# Microcontroller.net
KiCad netlist of a schematic drawn in Altium Designer
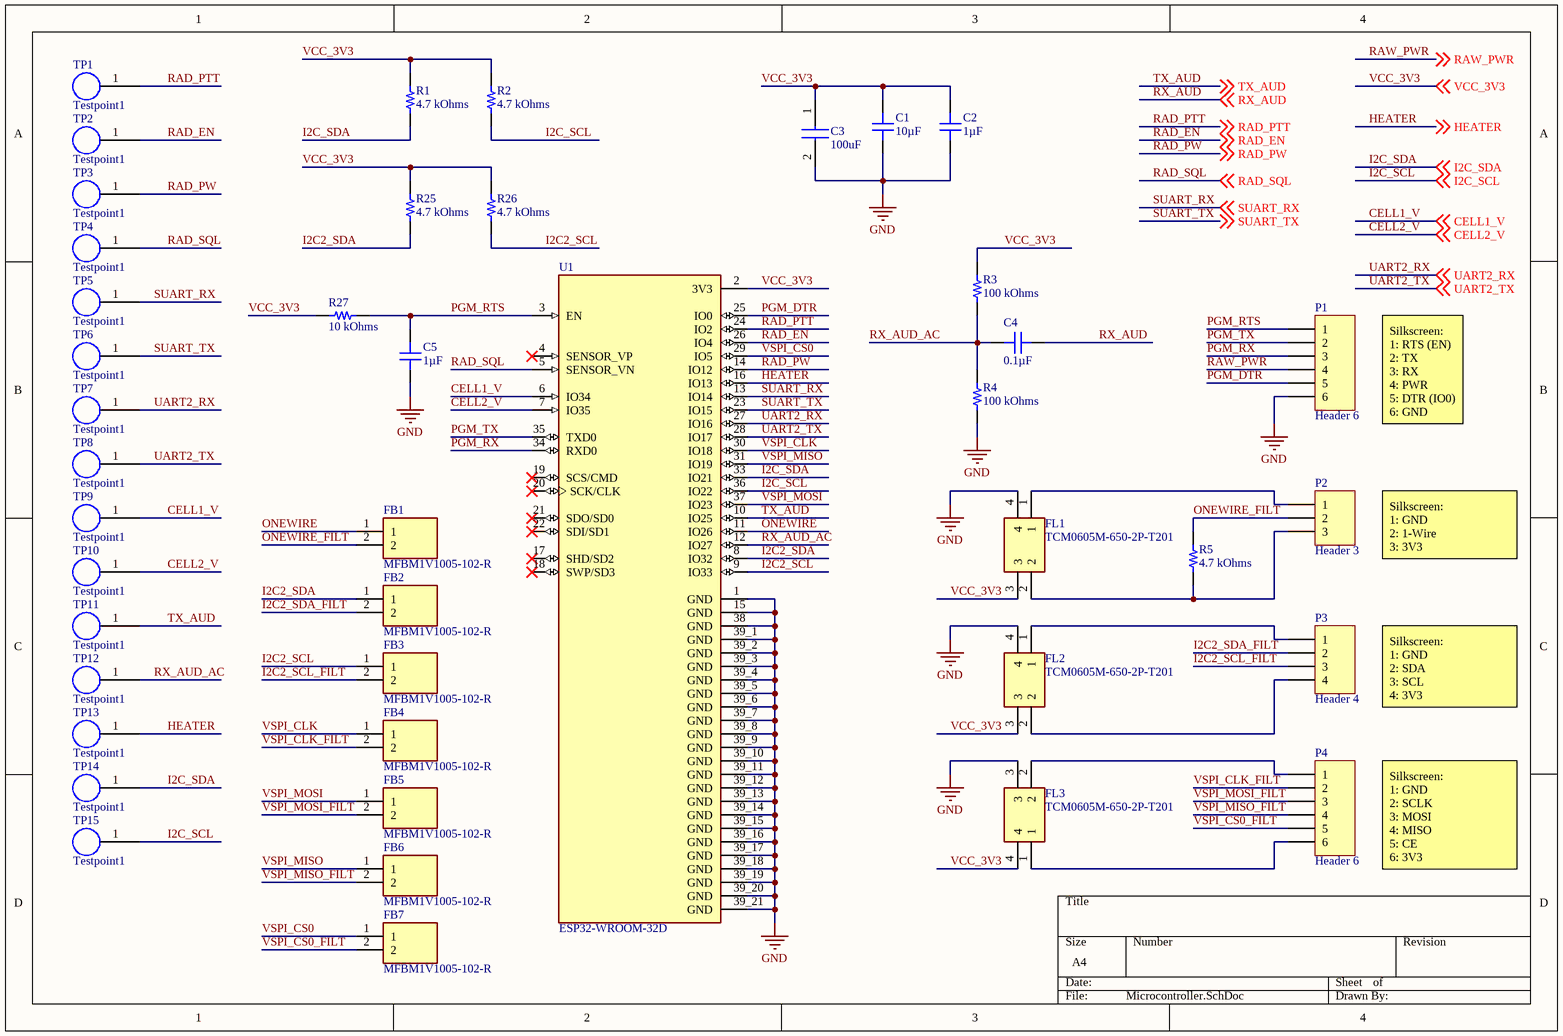
[diagram p0: Microcontroller.SchDoc]

(export (version "E")
  (design (tool "Eeschema 10.0.6"))
  (components
    (comp (ref "C1")
      (value "10µF")
      (footprint "CAP 0402_1005")
      (description "CAP CER 10UF 6.3V X5R 0402")
      (fields (field (name "PART NUMBER") "C0402C106M9PAC7867") (field (name "MANUFACTURER") "KEMET"))
      (libsource (lib "Celestial Altium Library - altium_library") (part "Capacitor"))
    )
    (comp (ref "C2")
      (value "1µF")
      (footprint "CAP 0402_1005")
      (description "CAP CER 1UF 16V X5R 0402")
      (fields (field (name "PART NUMBER") "0402YD105KAT2A") (field (name "MANUFACTURER") "AVX Corporation"))
      (libsource (lib "Celestial Altium Library - altium_library") (part "Capacitor"))
    )
    (comp (ref "C3")
      (value "100uF")
      (footprint "SamacSys:CAPC3225X270N")
      (description "Capacitor")
      (fields
        (field (name "MOUSER2 PART NUMBER") "81-GRM32EC70J107ME5L")
        (field (name "MANUFACTURER_PART_NUMBER") "GRM32EC70J107ME15L")
      )
      (libsource (lib "*") (part "GRM32EC70J107ME15L"))
    )
    (comp (ref "C4")
      (value "0.1µF")
      (footprint "CAP 0402_1005")
      (description "CAP CER 0.1UF 6.3V X5R 0402")
      (fields (field (name "PART NUMBER") "C0402C104K9PACTU") (field (name "MANUFACTURER") "KEMET"))
      (libsource (lib "Celestial Altium Library - altium_library") (part "Capacitor"))
    )
    (comp (ref "C5")
      (value "1µF")
      (footprint "CAP 0402_1005")
      (description "CAP CER 1UF 16V X5R 0402")
      (fields (field (name "PART NUMBER") "0402YD105KAT2A") (field (name "MANUFACTURER") "AVX Corporation"))
      (libsource (lib "Celestial Altium Library - altium_library") (part "Capacitor"))
    )
    (comp (ref "FB1")
      (value "MFBM1V1005-102-R")
      (footprint "SamacSys:BEADC1005X65N")
      (description "Ferrite Bead")
      (fields (field (name "MANUFACTURER_PART_NUMBER") "MFBM1V1005-101-R"))
      (libsource (lib "SamacSys") (part "MFBM1V1005-102-R"))
    )
    (comp (ref "FB2")
      (value "MFBM1V1005-102-R")
      (footprint "SamacSys:BEADC1005X65N")
      (description "Ferrite Bead")
      (fields (field (name "MANUFACTURER_PART_NUMBER") "MFBM1V1005-101-R"))
      (libsource (lib "SamacSys") (part "MFBM1V1005-102-R"))
    )
    (comp (ref "FB3")
      (value "MFBM1V1005-102-R")
      (footprint "SamacSys:BEADC1005X65N")
      (description "Ferrite Bead")
      (fields (field (name "MANUFACTURER_PART_NUMBER") "MFBM1V1005-101-R"))
      (libsource (lib "SamacSys") (part "MFBM1V1005-102-R"))
    )
    (comp (ref "FB4")
      (value "MFBM1V1005-102-R")
      (footprint "SamacSys:BEADC1005X65N")
      (description "Ferrite Bead")
      (fields (field (name "MANUFACTURER_PART_NUMBER") "MFBM1V1005-101-R"))
      (libsource (lib "SamacSys") (part "MFBM1V1005-102-R"))
    )
    (comp (ref "FB5")
      (value "MFBM1V1005-102-R")
      (footprint "SamacSys:BEADC1005X65N")
      (description "Ferrite Bead")
      (fields (field (name "MANUFACTURER_PART_NUMBER") "MFBM1V1005-101-R"))
      (libsource (lib "SamacSys") (part "MFBM1V1005-102-R"))
    )
    (comp (ref "FB6")
      (value "MFBM1V1005-102-R")
      (footprint "SamacSys:BEADC1005X65N")
      (description "Ferrite Bead")
      (fields (field (name "MANUFACTURER_PART_NUMBER") "MFBM1V1005-101-R"))
      (libsource (lib "SamacSys") (part "MFBM1V1005-102-R"))
    )
    (comp (ref "FB7")
      (value "MFBM1V1005-102-R")
      (footprint "SamacSys:BEADC1005X65N")
      (description "Ferrite Bead")
      (fields (field (name "MANUFACTURER_PART_NUMBER") "MFBM1V1005-101-R"))
      (libsource (lib "SamacSys") (part "MFBM1V1005-102-R"))
    )
    (comp (ref "FL1")
      (value "TCM0605M-650-2P-T201")
      (footprint "SamacSys:TCM0605M")
      (description "Filter")
      (libsource (lib "*") (part "TCM0605M-650-2P-T201"))
    )
    (comp (ref "FL2")
      (value "TCM0605M-650-2P-T201")
      (footprint "SamacSys:TCM0605M")
      (description "Filter")
      (libsource (lib "*") (part "TCM0605M-650-2P-T201"))
    )
    (comp (ref "FL3")
      (value "TCM0605M-650-2P-T201")
      (footprint "SamacSys:TCM0605M")
      (description "Filter")
      (libsource (lib "") (part "TCM0605M-650-2P-T201_1"))
    )
    (comp (ref "P1")
      (value "Header 6")
      (footprint "HDR1X6")
      (description "Header, 6-Pin")
      (fields (field (name "PUBLISHER") "Altium Limited"))
      (libsource (lib "Miscellaneous Connectors") (part "Header 6"))
    )
    (comp (ref "P2")
      (value "Header 3")
      (footprint "HDR1X3")
      (description "Header, 3-Pin")
      (fields (field (name "PUBLISHER") "Altium Limited"))
      (libsource (lib "Miscellaneous Connectors") (part "Header 3"))
    )
    (comp (ref "P3")
      (value "Header 4")
      (footprint "HDR1X4")
      (description "Header, 4-Pin")
      (fields (field (name "PUBLISHER") "Altium Limited"))
      (libsource (lib "Miscellaneous Connectors") (part "Header 4"))
    )
    (comp (ref "P4")
      (value "Header 6")
      (footprint "HDR1X6")
      (description "Header, 6-Pin")
      (fields (field (name "PUBLISHER") "Altium Limited"))
      (libsource (lib "Miscellaneous Connectors") (part "Header 6"))
    )
    (comp (ref "R1")
      (value "4.7 kOhms")
      (footprint "RES 0402_1005")
      (description "RES SMD 4.7K OHM 5% 1/16W 0402")
      (fields (field (name "PART NUMBER") "CRCW04024K70JNEDC") (field (name "MANUFACTURER") "Vishay Dale"))
      (libsource (lib "Celestial Altium Library - altium_library") (part "Resistor"))
    )
    (comp (ref "R2")
      (value "4.7 kOhms")
      (footprint "RES 0402_1005")
      (description "RES SMD 4.7K OHM 5% 1/16W 0402")
      (fields (field (name "PART NUMBER") "CRCW04024K70JNEDC") (field (name "MANUFACTURER") "Vishay Dale"))
      (libsource (lib "Celestial Altium Library - altium_library") (part "Resistor"))
    )
    (comp (ref "R3")
      (value "100 kOhms")
      (footprint "RES 0402_1005")
      (description "RES SMD 100K OHM 1% 1/16W 0402")
      (fields (field (name "PART NUMBER") "AC0402FR-07100KL") (field (name "MANUFACTURER") "Yageo"))
      (libsource (lib "Celestial Altium Library - altium_library") (part "Resistor"))
    )
    (comp (ref "R4")
      (value "100 kOhms")
      (footprint "RES 0402_1005")
      (description "RES SMD 100K OHM 1% 1/16W 0402")
      (fields (field (name "PART NUMBER") "AC0402FR-07100KL") (field (name "MANUFACTURER") "Yageo"))
      (libsource (lib "Celestial Altium Library - altium_library") (part "Resistor"))
    )
    (comp (ref "R5")
      (value "4.7 kOhms")
      (footprint "RES 0402_1005")
      (description "RES SMD 4.7K OHM 5% 1/16W 0402")
      (fields (field (name "PART NUMBER") "CRCW04024K70JNEDC") (field (name "MANUFACTURER") "Vishay Dale"))
      (libsource (lib "Celestial Altium Library - altium_library") (part "Resistor"))
    )
    (comp (ref "R25")
      (value "4.7 kOhms")
      (footprint "RES 0402_1005")
      (description "RES SMD 4.7K OHM 5% 1/16W 0402")
      (fields (field (name "PART NUMBER") "CRCW04024K70JNEDC") (field (name "MANUFACTURER") "Vishay Dale"))
      (libsource (lib "Celestial Altium Library - altium_library") (part "Resistor"))
    )
    (comp (ref "R26")
      (value "4.7 kOhms")
      (footprint "RES 0402_1005")
      (description "RES SMD 4.7K OHM 5% 1/16W 0402")
      (fields (field (name "PART NUMBER") "CRCW04024K70JNEDC") (field (name "MANUFACTURER") "Vishay Dale"))
      (libsource (lib "Celestial Altium Library - altium_library") (part "Resistor"))
    )
    (comp (ref "R27")
      (value "10 kOhms")
      (footprint "RES 0402_1005")
      (description "RES SMD 10K OHM 0.1% 1/16W 0402")
      (fields
        (field (name "PART NUMBER") "CPF0402B10KE1")
        (field (name "MANUFACTURER") "TE Connectivity Passive Product")
      )
      (libsource (lib "Celestial Altium Library - altium_library") (part "Resistor"))
    )
    (comp (ref "TP1")
      (value "Testpoint1")
      (footprint "Testpoint1")
      (libsource (lib "SamacSys") (part "Testpoint1"))
    )
    (comp (ref "TP2")
      (value "Testpoint1")
      (footprint "Testpoint1")
      (libsource (lib "SamacSys") (part "Testpoint1"))
    )
    (comp (ref "TP3")
      (value "Testpoint1")
      (footprint "Testpoint1")
      (libsource (lib "SamacSys") (part "Testpoint1"))
    )
    (comp (ref "TP4")
      (value "Testpoint1")
      (footprint "Testpoint1")
      (libsource (lib "SamacSys") (part "Testpoint1"))
    )
    (comp (ref "TP5")
      (value "Testpoint1")
      (footprint "Testpoint1")
      (libsource (lib "SamacSys") (part "Testpoint1"))
    )
    (comp (ref "TP6")
      (value "Testpoint1")
      (footprint "Testpoint1")
      (libsource (lib "SamacSys") (part "Testpoint1"))
    )
    (comp (ref "TP7")
      (value "Testpoint1")
      (footprint "Testpoint1")
      (libsource (lib "SamacSys") (part "Testpoint1"))
    )
    (comp (ref "TP8")
      (value "Testpoint1")
      (footprint "Testpoint1")
      (libsource (lib "SamacSys") (part "Testpoint1"))
    )
    (comp (ref "TP9")
      (value "Testpoint1")
      (footprint "Testpoint1")
      (libsource (lib "SamacSys") (part "Testpoint1"))
    )
    (comp (ref "TP10")
      (value "Testpoint1")
      (footprint "Testpoint1")
      (libsource (lib "SamacSys") (part "Testpoint1"))
    )
    (comp (ref "TP11")
      (value "Testpoint1")
      (footprint "Testpoint1")
      (libsource (lib "SamacSys") (part "Testpoint1"))
    )
    (comp (ref "TP12")
      (value "Testpoint1")
      (footprint "Testpoint1")
      (libsource (lib "SamacSys") (part "Testpoint1"))
    )
    (comp (ref "TP13")
      (value "Testpoint1")
      (footprint "Testpoint1")
      (libsource (lib "SamacSys") (part "Testpoint1"))
    )
    (comp (ref "TP14")
      (value "Testpoint1")
      (footprint "Testpoint1")
      (libsource (lib "SamacSys") (part "Testpoint1"))
    )
    (comp (ref "TP15")
      (value "Testpoint1")
      (footprint "Testpoint1")
      (libsource (lib "SamacSys") (part "Testpoint1"))
    )
    (comp (ref "U1")
      (value "ESP32-WROOM-32D")
      (footprint "MODULE_ESP32-WROOM-32D")
      (fields (field (name "MF") "Espressif Systems"))
      (libsource (lib "ESP32-WROOM-32D") (part "ESP32-WROOM-32D"))
    )
  )
  (nets
    (net (code "1") (name "/I2C2_SCL") (class "Default")
      (node (ref "FB3") (pin "1") (pinfunction "1_1") (pintype "passive"))
      (node (ref "R26") (pin "1") (pinfunction "1_1") (pintype "passive"))
      (node (ref "U1") (pin "9") (pinfunction "IO33_9") (pintype "bidirectional"))
    )
    (net (code "2") (name "/I2C2_SCL_FILT") (class "Default")
      (node (ref "FB3") (pin "2") (pinfunction "2_2") (pintype "passive"))
      (node (ref "P3") (pin "3") (pinfunction "3_3") (pintype "passive"))
    )
    (net (code "3") (name "/I2C2_SDA") (class "Default")
      (node (ref "FB2") (pin "1") (pinfunction "1_1") (pintype "passive"))
      (node (ref "R25") (pin "1") (pinfunction "1_1") (pintype "passive"))
      (node (ref "U1") (pin "8") (pinfunction "IO32_8") (pintype "bidirectional"))
    )
    (net (code "4") (name "/I2C2_SDA_FILT") (class "Default")
      (node (ref "FB2") (pin "2") (pinfunction "2_2") (pintype "passive"))
      (node (ref "P3") (pin "2") (pinfunction "2_2") (pintype "passive"))
    )
    (net (code "5") (name "/ONEWIRE") (class "Default")
      (node (ref "FB1") (pin "1") (pinfunction "1_1") (pintype "passive"))
      (node (ref "U1") (pin "11") (pinfunction "IO26_11") (pintype "bidirectional"))
    )
    (net (code "6") (name "/ONEWIRE_FILT") (class "Default")
      (node (ref "FB1") (pin "2") (pinfunction "2_2") (pintype "passive"))
      (node (ref "P2") (pin "2") (pinfunction "2_2") (pintype "passive"))
      (node (ref "R5") (pin "2") (pinfunction "2_2") (pintype "passive"))
    )
    (net (code "7") (name "/PGM_DTR") (class "Default")
      (node (ref "P1") (pin "5") (pinfunction "5_5") (pintype "passive"))
      (node (ref "U1") (pin "25") (pinfunction "IO0_25") (pintype "bidirectional"))
    )
    (net (code "8") (name "/PGM_RTS") (class "Default")
      (node (ref "C5") (pin "2") (pinfunction "2_2") (pintype "passive"))
      (node (ref "P1") (pin "1") (pinfunction "1_1") (pintype "passive"))
      (node (ref "R27") (pin "2") (pinfunction "2_2") (pintype "passive"))
      (node (ref "U1") (pin "3") (pinfunction "EN_3") (pintype "input"))
    )
    (net (code "9") (name "/PGM_RX") (class "Default")
      (node (ref "P1") (pin "3") (pinfunction "3_3") (pintype "passive"))
      (node (ref "U1") (pin "34") (pinfunction "RXD0_34") (pintype "bidirectional"))
    )
    (net (code "10") (name "/PGM_TX") (class "Default")
      (node (ref "P1") (pin "2") (pinfunction "2_2") (pintype "passive"))
      (node (ref "U1") (pin "35") (pinfunction "TXD0_35") (pintype "bidirectional"))
    )
    (net (code "11") (name "/RX_AUD_AC") (class "Default")
      (node (ref "C4") (pin "2") (pinfunction "2_2") (pintype "passive"))
      (node (ref "R3") (pin "1") (pinfunction "1_1") (pintype "passive"))
      (node (ref "R4") (pin "2") (pinfunction "2_2") (pintype "passive"))
      (node (ref "TP12") (pin "1") (pinfunction "1_1") (pintype "passive"))
      (node (ref "U1") (pin "12") (pinfunction "IO27_12") (pintype "bidirectional"))
    )
    (net (code "12") (name "/VSPI_CLK") (class "Default")
      (node (ref "FB4") (pin "1") (pinfunction "1_1") (pintype "passive"))
      (node (ref "U1") (pin "30") (pinfunction "IO18_30") (pintype "bidirectional"))
    )
    (net (code "13") (name "/VSPI_CLK_FILT") (class "Default")
      (node (ref "FB4") (pin "2") (pinfunction "2_2") (pintype "passive"))
      (node (ref "P4") (pin "2") (pinfunction "2_2") (pintype "passive"))
    )
    (net (code "14") (name "/VSPI_CS0") (class "Default")
      (node (ref "FB7") (pin "1") (pinfunction "1_1") (pintype "passive"))
      (node (ref "U1") (pin "29") (pinfunction "IO5_29") (pintype "bidirectional"))
    )
    (net (code "15") (name "/VSPI_CS0_FILT") (class "Default")
      (node (ref "FB7") (pin "2") (pinfunction "2_2") (pintype "passive"))
      (node (ref "P4") (pin "5") (pinfunction "5_5") (pintype "passive"))
    )
    (net (code "16") (name "/VSPI_MISO") (class "Default")
      (node (ref "FB6") (pin "1") (pinfunction "1_1") (pintype "passive"))
      (node (ref "U1") (pin "31") (pinfunction "IO19_31") (pintype "bidirectional"))
    )
    (net (code "17") (name "/VSPI_MISO_FILT") (class "Default")
      (node (ref "FB6") (pin "2") (pinfunction "2_2") (pintype "passive"))
      (node (ref "P4") (pin "4") (pinfunction "4_4") (pintype "passive"))
    )
    (net (code "18") (name "/VSPI_MOSI") (class "Default")
      (node (ref "FB5") (pin "1") (pinfunction "1_1") (pintype "passive"))
      (node (ref "U1") (pin "37") (pinfunction "IO23_37") (pintype "bidirectional"))
    )
    (net (code "19") (name "/VSPI_MOSI_FILT") (class "Default")
      (node (ref "FB5") (pin "2") (pinfunction "2_2") (pintype "passive"))
      (node (ref "P4") (pin "3") (pinfunction "3_3") (pintype "passive"))
    )
    (net (code "20") (name "CELL1_V") (class "Default")
      (node (ref "TP9") (pin "1") (pinfunction "1_1") (pintype "passive"))
      (node (ref "U1") (pin "6") (pinfunction "IO34_6") (pintype "input"))
    )
    (net (code "21") (name "CELL2_V") (class "Default")
      (node (ref "TP10") (pin "1") (pinfunction "1_1") (pintype "passive"))
      (node (ref "U1") (pin "7") (pinfunction "IO35_7") (pintype "input"))
    )
    (net (code "22") (name "GND") (class "Default")
      (node (ref "C1") (pin "1") (pinfunction "1_1") (pintype "passive"))
      (node (ref "C2") (pin "1") (pinfunction "1_1") (pintype "passive"))
      (node (ref "C3") (pin "2") (pinfunction "2_2") (pintype "passive"))
      (node (ref "C5") (pin "1") (pinfunction "1_1") (pintype "passive"))
      (node (ref "FL1") (pin "4") (pinfunction "4_4") (pintype "passive"))
      (node (ref "FL2") (pin "4") (pinfunction "4_4") (pintype "passive"))
      (node (ref "FL3") (pin "3") (pinfunction "3_3") (pintype "passive"))
      (node (ref "P1") (pin "6") (pinfunction "6_6") (pintype "passive"))
      (node (ref "R4") (pin "1") (pinfunction "1_1") (pintype "passive"))
      (node (ref "U1") (pin "1") (pinfunction "GND_1") (pintype "power_in"))
      (node (ref "U1") (pin "15") (pinfunction "GND_15") (pintype "power_in"))
      (node (ref "U1") (pin "38") (pinfunction "GND_38") (pintype "power_in"))
      (node (ref "U1") (pin "39_1") (pinfunction "GND_39_1") (pintype "power_in"))
      (node (ref "U1") (pin "39_10") (pinfunction "GND_39_10") (pintype "power_in"))
      (node (ref "U1") (pin "39_11") (pinfunction "GND_39_11") (pintype "power_in"))
      (node (ref "U1") (pin "39_12") (pinfunction "GND_39_12") (pintype "power_in"))
      (node (ref "U1") (pin "39_13") (pinfunction "GND_39_13") (pintype "power_in"))
      (node (ref "U1") (pin "39_14") (pinfunction "GND_39_14") (pintype "power_in"))
      (node (ref "U1") (pin "39_15") (pinfunction "GND_39_15") (pintype "power_in"))
      (node (ref "U1") (pin "39_16") (pinfunction "GND_39_16") (pintype "power_in"))
      (node (ref "U1") (pin "39_17") (pinfunction "GND_39_17") (pintype "power_in"))
      (node (ref "U1") (pin "39_18") (pinfunction "GND_39_18") (pintype "power_in"))
      (node (ref "U1") (pin "39_19") (pinfunction "GND_39_19") (pintype "power_in"))
      (node (ref "U1") (pin "39_2") (pinfunction "GND_39_2") (pintype "power_in"))
      (node (ref "U1") (pin "39_20") (pinfunction "GND_39_20") (pintype "power_in"))
      (node (ref "U1") (pin "39_21") (pinfunction "GND_39_21") (pintype "power_in"))
      (node (ref "U1") (pin "39_3") (pinfunction "GND_39_3") (pintype "power_in"))
      (node (ref "U1") (pin "39_4") (pinfunction "GND_39_4") (pintype "power_in"))
      (node (ref "U1") (pin "39_5") (pinfunction "GND_39_5") (pintype "power_in"))
      (node (ref "U1") (pin "39_6") (pinfunction "GND_39_6") (pintype "power_in"))
      (node (ref "U1") (pin "39_7") (pinfunction "GND_39_7") (pintype "power_in"))
      (node (ref "U1") (pin "39_8") (pinfunction "GND_39_8") (pintype "power_in"))
      (node (ref "U1") (pin "39_9") (pinfunction "GND_39_9") (pintype "power_in"))
    )
    (net (code "23") (name "HEATER") (class "Default")
      (node (ref "TP13") (pin "1") (pinfunction "1_1") (pintype "passive"))
      (node (ref "U1") (pin "16") (pinfunction "IO13_16") (pintype "bidirectional"))
    )
    (net (code "24") (name "I2C_SCL") (class "Default")
      (node (ref "R2") (pin "1") (pinfunction "1_1") (pintype "passive"))
      (node (ref "TP15") (pin "1") (pinfunction "1_1") (pintype "passive"))
      (node (ref "U1") (pin "36") (pinfunction "IO22_36") (pintype "bidirectional"))
    )
    (net (code "25") (name "I2C_SDA") (class "Default")
      (node (ref "R1") (pin "1") (pinfunction "1_1") (pintype "passive"))
      (node (ref "TP14") (pin "1") (pinfunction "1_1") (pintype "passive"))
      (node (ref "U1") (pin "33") (pinfunction "IO21_33") (pintype "bidirectional"))
    )
    (net (code "26") (name "Net-(FL1-Pad1)") (class "Default")
      (node (ref "FL1") (pin "1") (pinfunction "1_1") (pintype "passive"))
      (node (ref "P2") (pin "1") (pinfunction "1_1") (pintype "passive"))
    )
    (net (code "27") (name "Net-(FL1-Pad2)") (class "Default")
      (node (ref "FL1") (pin "2") (pinfunction "2_2") (pintype "passive"))
      (node (ref "P2") (pin "3") (pinfunction "3_3") (pintype "passive"))
      (node (ref "R5") (pin "1") (pinfunction "1_1") (pintype "passive"))
    )
    (net (code "28") (name "Net-(FL2-Pad1)") (class "Default")
      (node (ref "FL2") (pin "1") (pinfunction "1_1") (pintype "passive"))
      (node (ref "P3") (pin "1") (pinfunction "1_1") (pintype "passive"))
    )
    (net (code "29") (name "Net-(FL2-Pad2)") (class "Default")
      (node (ref "FL2") (pin "2") (pinfunction "2_2") (pintype "passive"))
      (node (ref "P3") (pin "4") (pinfunction "4_4") (pintype "passive"))
    )
    (net (code "30") (name "Net-(FL3-Pad1)") (class "Default")
      (node (ref "FL3") (pin "1") (pinfunction "1_1") (pintype "passive"))
      (node (ref "P4") (pin "6") (pinfunction "6_6") (pintype "passive"))
    )
    (net (code "31") (name "Net-(FL3-Pad2)") (class "Default")
      (node (ref "FL3") (pin "2") (pinfunction "2_2") (pintype "passive"))
      (node (ref "P4") (pin "1") (pinfunction "1_1") (pintype "passive"))
    )
    (net (code "32") (name "RAD_EN") (class "Default")
      (node (ref "TP2") (pin "1") (pinfunction "1_1") (pintype "passive"))
      (node (ref "U1") (pin "26") (pinfunction "IO4_26") (pintype "bidirectional"))
    )
    (net (code "33") (name "RAD_PTT") (class "Default")
      (node (ref "TP1") (pin "1") (pinfunction "1_1") (pintype "passive"))
      (node (ref "U1") (pin "24") (pinfunction "IO2_24") (pintype "bidirectional"))
    )
    (net (code "34") (name "RAD_PW") (class "Default")
      (node (ref "TP3") (pin "1") (pinfunction "1_1") (pintype "passive"))
      (node (ref "U1") (pin "14") (pinfunction "IO12_14") (pintype "bidirectional"))
    )
    (net (code "35") (name "RAD_SQL") (class "Default")
      (node (ref "TP4") (pin "1") (pinfunction "1_1") (pintype "passive"))
      (node (ref "U1") (pin "5") (pinfunction "SENSOR_VN_5") (pintype "input"))
    )
    (net (code "36") (name "RAW_PWR") (class "Default")
      (node (ref "P1") (pin "4") (pinfunction "4_4") (pintype "passive"))
    )
    (net (code "37") (name "RX_AUD") (class "Default")
      (node (ref "C4") (pin "1") (pinfunction "1_1") (pintype "passive"))
    )
    (net (code "38") (name "SUART_RX") (class "Default")
      (node (ref "TP5") (pin "1") (pinfunction "1_1") (pintype "passive"))
      (node (ref "U1") (pin "13") (pinfunction "IO14_13") (pintype "bidirectional"))
    )
    (net (code "39") (name "SUART_TX") (class "Default")
      (node (ref "TP6") (pin "1") (pinfunction "1_1") (pintype "passive"))
      (node (ref "U1") (pin "23") (pinfunction "IO15_23") (pintype "bidirectional"))
    )
    (net (code "40") (name "TX_AUD") (class "Default")
      (node (ref "TP11") (pin "1") (pinfunction "1_1") (pintype "passive"))
      (node (ref "U1") (pin "10") (pinfunction "IO25_10") (pintype "bidirectional"))
    )
    (net (code "41") (name "UART2_RX") (class "Default")
      (node (ref "TP7") (pin "1") (pinfunction "1_1") (pintype "passive"))
      (node (ref "U1") (pin "27") (pinfunction "IO16_27") (pintype "bidirectional"))
    )
    (net (code "42") (name "UART2_TX") (class "Default")
      (node (ref "TP8") (pin "1") (pinfunction "1_1") (pintype "passive"))
      (node (ref "U1") (pin "28") (pinfunction "IO17_28") (pintype "bidirectional"))
    )
    (net (code "43") (name "VCC_3V3") (class "Default")
      (node (ref "C1") (pin "2") (pinfunction "2_2") (pintype "passive"))
      (node (ref "C2") (pin "2") (pinfunction "2_2") (pintype "passive"))
      (node (ref "C3") (pin "1") (pinfunction "1_1") (pintype "passive"))
      (node (ref "FL1") (pin "3") (pinfunction "3_3") (pintype "passive"))
      (node (ref "FL2") (pin "3") (pinfunction "3_3") (pintype "passive"))
      (node (ref "FL3") (pin "4") (pinfunction "4_4") (pintype "passive"))
      (node (ref "R1") (pin "2") (pinfunction "2_2") (pintype "passive"))
      (node (ref "R2") (pin "2") (pinfunction "2_2") (pintype "passive"))
      (node (ref "R25") (pin "2") (pinfunction "2_2") (pintype "passive"))
      (node (ref "R26") (pin "2") (pinfunction "2_2") (pintype "passive"))
      (node (ref "R27") (pin "1") (pinfunction "1_1") (pintype "passive"))
      (node (ref "R3") (pin "2") (pinfunction "2_2") (pintype "passive"))
      (node (ref "U1") (pin "2") (pinfunction "3V3_2") (pintype "power_in"))
    )
    (net (code "44") (name "unconnected-(U1-SCK{slash}CLK-Pad20)") (class "Default")
      (node (ref "U1") (pin "20") (pinfunction "SCK/CLK_20") (pintype "bidirectional+no_connect"))
    )
    (net (code "45") (name "unconnected-(U1-SCS{slash}CMD-Pad19)") (class "Default")
      (node (ref "U1") (pin "19") (pinfunction "SCS/CMD_19") (pintype "bidirectional+no_connect"))
    )
    (net (code "46") (name "unconnected-(U1-SDI{slash}SD1-Pad22)") (class "Default")
      (node (ref "U1") (pin "22") (pinfunction "SDI/SD1_22") (pintype "bidirectional+no_connect"))
    )
    (net (code "47") (name "unconnected-(U1-SDO{slash}SD0-Pad21)") (class "Default")
      (node (ref "U1") (pin "21") (pinfunction "SDO/SD0_21") (pintype "bidirectional+no_connect"))
    )
    (net (code "48") (name "unconnected-(U1-SENSOR_VP-Pad4)") (class "Default")
      (node (ref "U1") (pin "4") (pinfunction "SENSOR_VP_4") (pintype "input+no_connect"))
    )
    (net (code "49") (name "unconnected-(U1-SHD{slash}SD2-Pad17)") (class "Default")
      (node (ref "U1") (pin "17") (pinfunction "SHD/SD2_17") (pintype "bidirectional+no_connect"))
    )
    (net (code "50") (name "unconnected-(U1-SWP{slash}SD3-Pad18)") (class "Default")
      (node (ref "U1") (pin "18") (pinfunction "SWP/SD3_18") (pintype "bidirectional+no_connect"))
    )
  )
)
